# MSP430F5438A.net
KiCad netlist of a schematic drawn in Altium Designer
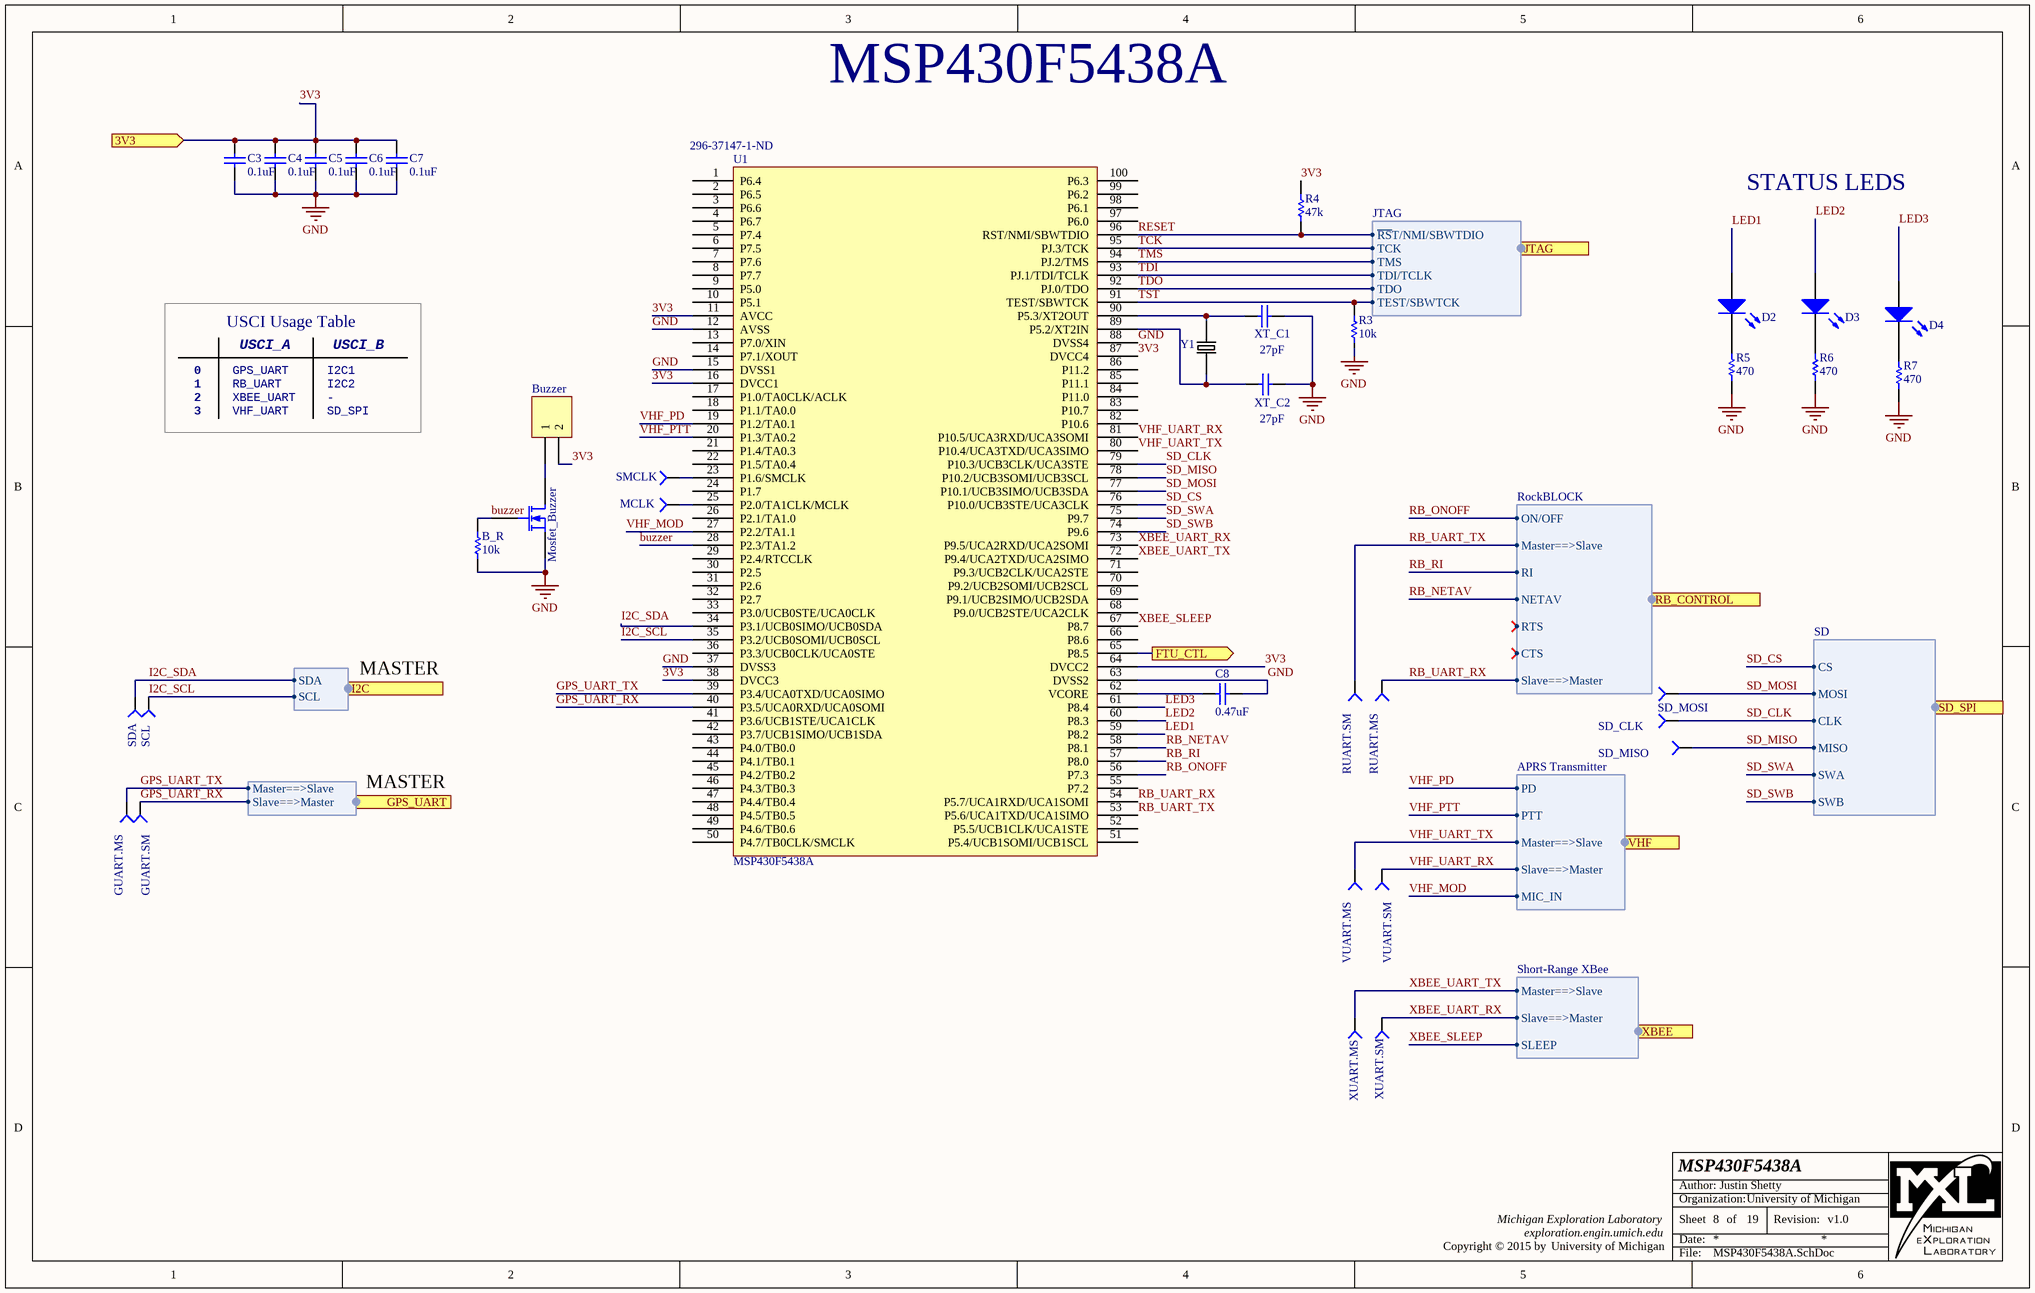
[diagram p0: MSP430F5438A.SchDoc]

(export (version "E")
  (design (tool "Eeschema 10.0.6"))
  (components
    (comp (ref "B_R")
      (value "10k")
      (footprint "J1-0603")
      (description "Resistive element")
      (fields (field (name "Comment") "Resistor"))
      (libsource (lib "MXLab Generic") (part "Resistor"))
    )
    (comp (ref "C3")
      (value "0.1uF")
      (footprint "1608[0603]")
      (description "Capacitor Ceramic")
      (libsource (lib "MXLab Generic") (part "Capacitor Ceramic"))
    )
    (comp (ref "C4")
      (value "0.1uF")
      (footprint "1608[0603]")
      (description "Capacitor Ceramic")
      (libsource (lib "MXLab Generic") (part "Capacitor Ceramic"))
    )
    (comp (ref "C5")
      (value "0.1uF")
      (footprint "1608[0603]")
      (description "Capacitor Ceramic")
      (libsource (lib "MXLab Generic") (part "Capacitor Ceramic"))
    )
    (comp (ref "C6")
      (value "0.1uF")
      (footprint "1608[0603]")
      (description "Capacitor Ceramic")
      (libsource (lib "MXLab Generic") (part "Capacitor Ceramic"))
    )
    (comp (ref "C7")
      (value "0.1uF")
      (footprint "1608[0603]")
      (description "Capacitor Ceramic")
      (libsource (lib "MXLab Generic") (part "Capacitor Ceramic"))
    )
    (comp (ref "C8")
      (value "0.47uF")
      (footprint "1608[0603]")
      (description "Capacitor Ceramic")
      (libsource (lib "MXLab Generic") (part "Capacitor Ceramic"))
    )
    (comp (ref "D2") (value "LED") (footprint "J1-0603") (libsource (lib "MXLab Generic") (part "LED")))
    (comp (ref "D3") (value "LED") (footprint "J1-0603") (libsource (lib "MXLab Generic") (part "LED")))
    (comp (ref "D4") (value "LED") (footprint "J1-0603") (libsource (lib "MXLab Generic") (part "LED")))
    (comp (ref "GUART.MS")
      (value "Testpoint")
      (footprint "TESTPOINT")
      (description "Probe point for testing")
      (libsource (lib "MXLab Generic") (part "Testpoint"))
    )
    (comp (ref "GUART.SM")
      (value "Testpoint")
      (footprint "TESTPOINT")
      (description "Probe point for testing")
      (libsource (lib "MXLab Generic") (part "Testpoint"))
    )
    (comp (ref "MCLK")
      (value "Testpoint")
      (footprint "TESTPOINT")
      (description "Probe point for testing")
      (libsource (lib "MXLab Generic") (part "Testpoint"))
    )
    (comp (ref "Mosfet_Buzzer")
      (value "MOSFET-N")
      (footprint "SOT-23_M")
      (description "N-Channel MOSFET")
      (fields (field (name "PUBLISHER") "Altium Limited"))
      (libsource (lib "Miscellaneous Devices") (part "MOSFET-N"))
    )
    (comp (ref "P4")
      (value "Buzzer")
      (footprint "Buzzer")
      (description "Header, 2-Pin")
      (fields (field (name "PUBLISHER") "Altium Limited"))
      (libsource (lib "Miscellaneous Connectors") (part "Header 2"))
    )
    (comp (ref "R3")
      (value "10k")
      (footprint "J1-0603")
      (description "Resistive element")
      (fields (field (name "Comment") "Resistor"))
      (libsource (lib "MXLab Generic") (part "Resistor"))
    )
    (comp (ref "R4")
      (value "47k")
      (footprint "J1-0603")
      (description "Resistive element")
      (fields (field (name "Comment") "Resistor"))
      (libsource (lib "MXLab Generic") (part "Resistor"))
    )
    (comp (ref "R5")
      (value "470")
      (footprint "J1-0603")
      (description "Resistive element")
      (fields (field (name "Comment") "Resistor"))
      (libsource (lib "MXLab Generic") (part "Resistor"))
    )
    (comp (ref "R6")
      (value "470")
      (footprint "J1-0603")
      (description "Resistive element")
      (fields (field (name "Comment") "Resistor"))
      (libsource (lib "MXLab Generic") (part "Resistor"))
    )
    (comp (ref "R7")
      (value "470")
      (footprint "J1-0603")
      (description "Resistive element")
      (fields (field (name "Comment") "Resistor"))
      (libsource (lib "MXLab Generic") (part "Resistor"))
    )
    (comp (ref "RUART.MS")
      (value "Testpoint")
      (footprint "TESTPOINT")
      (description "Probe point for testing")
      (libsource (lib "MXLab Generic") (part "Testpoint"))
    )
    (comp (ref "RUART.SM")
      (value "Testpoint")
      (footprint "TESTPOINT")
      (description "Probe point for testing")
      (libsource (lib "MXLab Generic") (part "Testpoint"))
    )
    (comp (ref "SCL")
      (value "Testpoint")
      (footprint "TESTPOINT")
      (description "Probe point for testing")
      (libsource (lib "MXLab Generic") (part "Testpoint"))
    )
    (comp (ref "SDA")
      (value "Testpoint")
      (footprint "TESTPOINT")
      (description "Probe point for testing")
      (libsource (lib "MXLab Generic") (part "Testpoint"))
    )
    (comp (ref "SD_CLK")
      (value "Testpoint")
      (footprint "TESTPOINT")
      (description "Probe point for testing")
      (libsource (lib "MXLab Generic") (part "Testpoint"))
    )
    (comp (ref "SD_MISO")
      (value "Testpoint")
      (footprint "TESTPOINT")
      (description "Probe point for testing")
      (libsource (lib "MXLab Generic") (part "Testpoint"))
    )
    (comp (ref "SD_MOSI")
      (value "Testpoint")
      (footprint "TESTPOINT")
      (description "Probe point for testing")
      (libsource (lib "MXLab Generic") (part "Testpoint"))
    )
    (comp (ref "SMCLK")
      (value "Testpoint")
      (footprint "TESTPOINT")
      (description "Probe point for testing")
      (libsource (lib "MXLab Generic") (part "Testpoint"))
    )
    (comp (ref "U1")
      (value "MSP430F5438A")
      (footprint "TSQFP50P1600X1600X160-100L")
      (fields
        (field (name "SUPPLIER PART NUMBER 1") "296-37147-1-ND")
        (field (name "MANUFACTURER") "Texas Instruments")
        (field (name "MANUFACTURER PART NUMBER") "MSP430F5438AIPZR")
      )
      (libsource (lib "ATACS_SCH_LIB") (part "MSP430F438IPZ"))
    )
    (comp (ref "VUART.MS")
      (value "Testpoint")
      (footprint "TESTPOINT")
      (description "Probe point for testing")
      (libsource (lib "MXLab Generic") (part "Testpoint"))
    )
    (comp (ref "VUART.SM")
      (value "Testpoint")
      (footprint "TESTPOINT")
      (description "Probe point for testing")
      (libsource (lib "MXLab Generic") (part "Testpoint"))
    )
    (comp (ref "XT_C1")
      (value "27pF")
      (footprint "1608[0603]")
      (description "Capacitor Ceramic")
      (libsource (lib "MXLab Generic") (part "Capacitor Ceramic"))
    )
    (comp (ref "XT_C2")
      (value "27pF")
      (footprint "1608[0603]")
      (description "Capacitor Ceramic")
      (libsource (lib "MXLab Generic") (part "Capacitor Ceramic"))
    )
    (comp (ref "XUART.MS")
      (value "Testpoint")
      (footprint "TESTPOINT")
      (description "Probe point for testing")
      (libsource (lib "MXLab Generic") (part "Testpoint"))
    )
    (comp (ref "XUART.SM")
      (value "Testpoint")
      (footprint "TESTPOINT")
      (description "Probe point for testing")
      (libsource (lib "MXLab Generic") (part "Testpoint"))
    )
    (comp (ref "Y1")
      (value "ECS-160-18-5PXEN-TR")
      (footprint "*XTAL_ECS-160-18-5PXEN-TR")
      (description "Crystal 16MHz 18pF 2-Pin SMD T/R")
      (fields (field (name "DIGI-KEY_PART_NUMBER") "XC1695CT-ND") (field (name "MF") "ECS Inc."))
      (libsource (lib "ATACS_SCH_LIB") (part "ECS-160-18-5PXEN-TR"))
    )
  )
  (nets
    (net (code "10") (name "/3V3") (class "Default")
      (node (ref "C3") (pin "2") (pinfunction "2_2") (pintype "passive"))
      (node (ref "C4") (pin "2") (pinfunction "2_2") (pintype "passive"))
      (node (ref "C5") (pin "2") (pinfunction "2_2") (pintype "passive"))
      (node (ref "C6") (pin "2") (pinfunction "2_2") (pintype "passive"))
      (node (ref "C7") (pin "2") (pinfunction "2_2") (pintype "passive"))
      (node (ref "P4") (pin "2") (pinfunction "2_2") (pintype "passive"))
      (node (ref "R4") (pin "1") (pinfunction "1_1") (pintype "passive"))
      (node (ref "U1") (pin "11") (pinfunction "AVCC_11") (pintype "passive"))
      (node (ref "U1") (pin "16") (pinfunction "DVCC1_16") (pintype "passive"))
      (node (ref "U1") (pin "38") (pinfunction "DVCC3_38") (pintype "passive"))
      (node (ref "U1") (pin "64") (pinfunction "DVCC2_64") (pintype "passive"))
      (node (ref "U1") (pin "87") (pinfunction "DVCC4_87") (pintype "passive"))
    )
    (net (code "11") (name "/FTU_CTL") (class "Default")
      (node (ref "U1") (pin "65") (pinfunction "P8.5_65") (pintype "passive"))
    )
    (net (code "12") (name "/GPS_UART_RX") (class "Default")
      (node (ref "GUART.SM") (pin "1") (pinfunction "1_1") (pintype "passive"))
      (node (ref "U1") (pin "40") (pinfunction "P3.5/UCA0RXD/UCA0SOMI_40") (pintype "passive"))
    )
    (net (code "13") (name "/GPS_UART_TX") (class "Default")
      (node (ref "GUART.MS") (pin "1") (pinfunction "1_1") (pintype "passive"))
      (node (ref "U1") (pin "39") (pinfunction "P3.4/UCA0TXD/UCA0SIMO_39") (pintype "passive"))
    )
    (net (code "14") (name "/I2C_SCL") (class "Default")
      (node (ref "SCL") (pin "1") (pinfunction "1_1") (pintype "passive"))
      (node (ref "U1") (pin "35") (pinfunction "P3.2/UCB0SOMI/UCB0SCL_35") (pintype "passive"))
    )
    (net (code "15") (name "/I2C_SDA") (class "Default")
      (node (ref "SDA") (pin "1") (pinfunction "1_1") (pintype "passive"))
      (node (ref "U1") (pin "34") (pinfunction "P3.1/UCB0SIMO/UCB0SDA_34") (pintype "passive"))
    )
    (net (code "16") (name "/LED1") (class "Default")
      (node (ref "D2") (pin "2") (pinfunction "K_2") (pintype "passive"))
      (node (ref "U1") (pin "59") (pinfunction "P8.2_59") (pintype "passive"))
    )
    (net (code "17") (name "/LED2") (class "Default")
      (node (ref "D3") (pin "2") (pinfunction "K_2") (pintype "passive"))
      (node (ref "U1") (pin "60") (pinfunction "P8.3_60") (pintype "passive"))
    )
    (net (code "18") (name "/LED3") (class "Default")
      (node (ref "D4") (pin "2") (pinfunction "K_2") (pintype "passive"))
      (node (ref "U1") (pin "61") (pinfunction "P8.4_61") (pintype "passive"))
    )
    (net (code "19") (name "/RB_NETAV") (class "Default")
      (node (ref "U1") (pin "58") (pinfunction "P8.1_58") (pintype "passive"))
    )
    (net (code "20") (name "/RB_ONOFF") (class "Default")
      (node (ref "U1") (pin "56") (pinfunction "P7.3_56") (pintype "passive"))
    )
    (net (code "21") (name "/RB_RI") (class "Default")
      (node (ref "U1") (pin "57") (pinfunction "P8.0_57") (pintype "passive"))
    )
    (net (code "22") (name "/RB_UART_RX") (class "Default")
      (node (ref "RUART.MS") (pin "1") (pinfunction "1_1") (pintype "passive"))
      (node (ref "U1") (pin "54") (pinfunction "P5.7/UCA1RXD/UCA1SOMI_54") (pintype "passive"))
    )
    (net (code "23") (name "/RB_UART_TX") (class "Default")
      (node (ref "RUART.SM") (pin "1") (pinfunction "1_1") (pintype "passive"))
      (node (ref "U1") (pin "53") (pinfunction "P5.6/UCA1TXD/UCA1SIMO_53") (pintype "passive"))
    )
    (net (code "24") (name "/RESET") (class "Default")
      (node (ref "R4") (pin "2") (pinfunction "2_2") (pintype "passive"))
      (node (ref "U1") (pin "96") (pinfunction "RST/NMI/SBWTDIO_96") (pintype "passive"))
    )
    (net (code "25") (name "/SD_CLK") (class "Default")
      (node (ref "SD_CLK") (pin "1") (pinfunction "1_1") (pintype "passive"))
      (node (ref "U1") (pin "79") (pinfunction "P10.3/UCB3CLK/UCA3STE_79") (pintype "passive"))
    )
    (net (code "26") (name "/SD_CS") (class "Default")
      (node (ref "U1") (pin "76") (pinfunction "P10.0/UCB3STE/UCA3CLK_76") (pintype "passive"))
    )
    (net (code "27") (name "/SD_MISO") (class "Default")
      (node (ref "SD_MISO") (pin "1") (pinfunction "1_1") (pintype "passive"))
      (node (ref "U1") (pin "78") (pinfunction "P10.2/UCB3SOMI/UCB3SCL_78") (pintype "passive"))
    )
    (net (code "28") (name "/SD_MOSI") (class "Default")
      (node (ref "SD_MOSI") (pin "1") (pinfunction "1_1") (pintype "passive"))
      (node (ref "U1") (pin "77") (pinfunction "P10.1/UCB3SIMO/UCB3SDA_77") (pintype "passive"))
    )
    (net (code "29") (name "/SD_SWA") (class "Default")
      (node (ref "U1") (pin "75") (pinfunction "P9.7_75") (pintype "passive"))
    )
    (net (code "30") (name "/SD_SWB") (class "Default")
      (node (ref "U1") (pin "74") (pinfunction "P9.6_74") (pintype "passive"))
    )
    (net (code "31") (name "/TCK") (class "Default")
      (node (ref "U1") (pin "95") (pinfunction "PJ.3/TCK_95") (pintype "passive"))
    )
    (net (code "32") (name "/TDI") (class "Default")
      (node (ref "U1") (pin "93") (pinfunction "PJ.1/TDI/TCLK_93") (pintype "passive"))
    )
    (net (code "33") (name "/TDO") (class "Default")
      (node (ref "U1") (pin "92") (pinfunction "PJ.0/TDO_92") (pintype "passive"))
    )
    (net (code "34") (name "/TMS") (class "Default")
      (node (ref "U1") (pin "94") (pinfunction "PJ.2/TMS_94") (pintype "passive"))
    )
    (net (code "35") (name "/TST") (class "Default")
      (node (ref "R3") (pin "2") (pinfunction "2_2") (pintype "passive"))
      (node (ref "U1") (pin "91") (pinfunction "TEST/SBWTCK_91") (pintype "passive"))
    )
    (net (code "36") (name "/VHF_MOD") (class "Default")
      (node (ref "U1") (pin "27") (pinfunction "P2.2/TA1.1_27") (pintype "passive"))
    )
    (net (code "37") (name "/VHF_PD") (class "Default")
      (node (ref "U1") (pin "19") (pinfunction "P1.2/TA0.1_19") (pintype "passive"))
    )
    (net (code "38") (name "/VHF_PTT") (class "Default")
      (node (ref "U1") (pin "20") (pinfunction "P1.3/TA0.2_20") (pintype "passive"))
    )
    (net (code "39") (name "/VHF_UART_RX") (class "Default")
      (node (ref "U1") (pin "81") (pinfunction "P10.5/UCA3RXD/UCA3SOMI_81") (pintype "passive"))
      (node (ref "VUART.SM") (pin "1") (pinfunction "1_1") (pintype "passive"))
    )
    (net (code "40") (name "/VHF_UART_TX") (class "Default")
      (node (ref "U1") (pin "80") (pinfunction "P10.4/UCA3TXD/UCA3SIMO_80") (pintype "passive"))
      (node (ref "VUART.MS") (pin "1") (pinfunction "1_1") (pintype "passive"))
    )
    (net (code "41") (name "/XBEE_SLEEP") (class "Default")
      (node (ref "U1") (pin "67") (pinfunction "P8.7_67") (pintype "passive"))
    )
    (net (code "42") (name "/XBEE_UART_RX") (class "Default")
      (node (ref "U1") (pin "73") (pinfunction "P9.5/UCA2RXD/UCA2SOMI_73") (pintype "passive"))
      (node (ref "XUART.SM") (pin "1") (pinfunction "1_1") (pintype "passive"))
    )
    (net (code "43") (name "/XBEE_UART_TX") (class "Default")
      (node (ref "U1") (pin "72") (pinfunction "P9.4/UCA2TXD/UCA2SIMO_72") (pintype "passive"))
      (node (ref "XUART.MS") (pin "1") (pinfunction "1_1") (pintype "passive"))
    )
    (net (code "44") (name "/buzzer") (class "Default")
      (node (ref "B_R") (pin "2") (pinfunction "2_2") (pintype "passive"))
      (node (ref "Mosfet_Buzzer") (pin "2") (pinfunction "G_2") (pintype "passive"))
      (node (ref "U1") (pin "28") (pinfunction "P2.3/TA1.2_28") (pintype "passive"))
    )
    (net (code "52") (name "GND") (class "Default")
      (node (ref "B_R") (pin "1") (pinfunction "1_1") (pintype "passive"))
      (node (ref "C3") (pin "1") (pinfunction "1_1") (pintype "passive"))
      (node (ref "C4") (pin "1") (pinfunction "1_1") (pintype "passive"))
      (node (ref "C5") (pin "1") (pinfunction "1_1") (pintype "passive"))
      (node (ref "C6") (pin "1") (pinfunction "1_1") (pintype "passive"))
      (node (ref "C7") (pin "1") (pinfunction "1_1") (pintype "passive"))
      (node (ref "C8") (pin "2") (pinfunction "2_2") (pintype "passive"))
      (node (ref "Mosfet_Buzzer") (pin "3") (pinfunction "S_3") (pintype "passive"))
      (node (ref "R3") (pin "1") (pinfunction "1_1") (pintype "passive"))
      (node (ref "R5") (pin "1") (pinfunction "1_1") (pintype "passive"))
      (node (ref "R6") (pin "1") (pinfunction "1_1") (pintype "passive"))
      (node (ref "R7") (pin "1") (pinfunction "1_1") (pintype "passive"))
      (node (ref "U1") (pin "12") (pinfunction "AVSS_12") (pintype "passive"))
      (node (ref "U1") (pin "15") (pinfunction "DVSS1_15") (pintype "passive"))
      (node (ref "U1") (pin "37") (pinfunction "DVSS3_37") (pintype "passive"))
      (node (ref "U1") (pin "63") (pinfunction "DVSS2_63") (pintype "passive"))
      (node (ref "U1") (pin "88") (pinfunction "DVSS4_88") (pintype "passive"))
      (node (ref "XT_C1") (pin "1") (pinfunction "1_1") (pintype "passive"))
      (node (ref "XT_C2") (pin "1") (pinfunction "1_1") (pintype "passive"))
    )
    (net (code "53") (name "Net-(D2-A)") (class "Default")
      (node (ref "D2") (pin "1") (pinfunction "A_1") (pintype "passive"))
      (node (ref "R5") (pin "2") (pinfunction "2_2") (pintype "passive"))
    )
    (net (code "54") (name "Net-(D3-A)") (class "Default")
      (node (ref "D3") (pin "1") (pinfunction "A_1") (pintype "passive"))
      (node (ref "R6") (pin "2") (pinfunction "2_2") (pintype "passive"))
    )
    (net (code "55") (name "Net-(D4-A)") (class "Default")
      (node (ref "D4") (pin "1") (pinfunction "A_1") (pintype "passive"))
      (node (ref "R7") (pin "2") (pinfunction "2_2") (pintype "passive"))
    )
    (net (code "56") (name "Net-(Mosfet_Buzzer-D)") (class "Default")
      (node (ref "Mosfet_Buzzer") (pin "1") (pinfunction "D_1") (pintype "passive"))
      (node (ref "P4") (pin "1") (pinfunction "1_1") (pintype "passive"))
    )
    (net (code "57") (name "Net-(U1-P1.6{slash}SMCLK)") (class "Default")
      (node (ref "SMCLK") (pin "1") (pinfunction "1_1") (pintype "passive"))
      (node (ref "U1") (pin "23") (pinfunction "P1.6/SMCLK_23") (pintype "passive"))
    )
    (net (code "58") (name "Net-(U1-P2.0{slash}TA1CLK{slash}MCLK)") (class "Default")
      (node (ref "MCLK") (pin "1") (pinfunction "1_1") (pintype "passive"))
      (node (ref "U1") (pin "25") (pinfunction "P2.0/TA1CLK/MCLK_25") (pintype "passive"))
    )
    (net (code "59") (name "Net-(U1-P5.2{slash}XT2IN)") (class "Default")
      (node (ref "U1") (pin "89") (pinfunction "P5.2/XT2IN_89") (pintype "passive"))
      (node (ref "XT_C2") (pin "2") (pinfunction "2_2") (pintype "passive"))
      (node (ref "Y1") (pin "1") (pinfunction "1_1") (pintype "passive"))
    )
    (net (code "60") (name "Net-(U1-P5.3{slash}XT2OUT)") (class "Default")
      (node (ref "U1") (pin "90") (pinfunction "P5.3/XT2OUT_90") (pintype "passive"))
      (node (ref "XT_C1") (pin "2") (pinfunction "2_2") (pintype "passive"))
      (node (ref "Y1") (pin "2") (pinfunction "2_2") (pintype "passive"))
    )
    (net (code "61") (name "Net-(U1-VCORE)") (class "Default")
      (node (ref "C8") (pin "1") (pinfunction "1_1") (pintype "passive"))
      (node (ref "U1") (pin "62") (pinfunction "VCORE_62") (pintype "passive"))
    )
    (net (code "62") (name "unconnected-(U1-P1.0{slash}TA0CLK{slash}ACLK-Pad17)") (class "Default")
      (node (ref "U1") (pin "17") (pinfunction "P1.0/TA0CLK/ACLK_17") (pintype "passive"))
    )
    (net (code "63") (name "unconnected-(U1-P1.1{slash}TA0.0-Pad18)") (class "Default")
      (node (ref "U1") (pin "18") (pinfunction "P1.1/TA0.0_18") (pintype "passive"))
    )
    (net (code "64") (name "unconnected-(U1-P1.4{slash}TA0.3-Pad21)") (class "Default")
      (node (ref "U1") (pin "21") (pinfunction "P1.4/TA0.3_21") (pintype "passive"))
    )
    (net (code "65") (name "unconnected-(U1-P1.5{slash}TA0.4-Pad22)") (class "Default")
      (node (ref "U1") (pin "22") (pinfunction "P1.5/TA0.4_22") (pintype "passive"))
    )
    (net (code "66") (name "unconnected-(U1-P1.7-Pad24)") (class "Default")
      (node (ref "U1") (pin "24") (pinfunction "P1.7_24") (pintype "passive"))
    )
    (net (code "67") (name "unconnected-(U1-P2.1{slash}TA1.0-Pad26)") (class "Default")
      (node (ref "U1") (pin "26") (pinfunction "P2.1/TA1.0_26") (pintype "passive"))
    )
    (net (code "68") (name "unconnected-(U1-P2.4{slash}RTCCLK-Pad29)") (class "Default")
      (node (ref "U1") (pin "29") (pinfunction "P2.4/RTCCLK_29") (pintype "passive"))
    )
    (net (code "69") (name "unconnected-(U1-P2.5-Pad30)") (class "Default")
      (node (ref "U1") (pin "30") (pinfunction "P2.5_30") (pintype "passive"))
    )
    (net (code "70") (name "unconnected-(U1-P2.6-Pad31)") (class "Default")
      (node (ref "U1") (pin "31") (pinfunction "P2.6_31") (pintype "passive"))
    )
    (net (code "71") (name "unconnected-(U1-P2.7-Pad32)") (class "Default")
      (node (ref "U1") (pin "32") (pinfunction "P2.7_32") (pintype "passive"))
    )
    (net (code "72") (name "unconnected-(U1-P3.0{slash}UCB0STE{slash}UCA0CLK-Pad33)") (class "Default")
      (node (ref "U1") (pin "33") (pinfunction "P3.0/UCB0STE/UCA0CLK_33") (pintype "passive"))
    )
    (net (code "73") (name "unconnected-(U1-P3.3{slash}UCB0CLK{slash}UCA0STE-Pad36)") (class "Default")
      (node (ref "U1") (pin "36") (pinfunction "P3.3/UCB0CLK/UCA0STE_36") (pintype "passive"))
    )
    (net (code "74") (name "unconnected-(U1-P3.6{slash}UCB1STE{slash}UCA1CLK-Pad41)") (class "Default")
      (node (ref "U1") (pin "41") (pinfunction "P3.6/UCB1STE/UCA1CLK_41") (pintype "passive"))
    )
    (net (code "75") (name "unconnected-(U1-P3.7{slash}UCB1SIMO{slash}UCB1SDA-Pad42)") (class "Default")
      (node (ref "U1") (pin "42") (pinfunction "P3.7/UCB1SIMO/UCB1SDA_42") (pintype "passive"))
    )
    (net (code "76") (name "unconnected-(U1-P4.0{slash}TB0.0-Pad43)") (class "Default")
      (node (ref "U1") (pin "43") (pinfunction "P4.0/TB0.0_43") (pintype "passive"))
    )
    (net (code "77") (name "unconnected-(U1-P4.1{slash}TB0.1-Pad44)") (class "Default")
      (node (ref "U1") (pin "44") (pinfunction "P4.1/TB0.1_44") (pintype "passive"))
    )
    (net (code "78") (name "unconnected-(U1-P4.2{slash}TB0.2-Pad45)") (class "Default")
      (node (ref "U1") (pin "45") (pinfunction "P4.2/TB0.2_45") (pintype "passive"))
    )
    (net (code "79") (name "unconnected-(U1-P4.3{slash}TB0.3-Pad46)") (class "Default")
      (node (ref "U1") (pin "46") (pinfunction "P4.3/TB0.3_46") (pintype "passive"))
    )
    (net (code "80") (name "unconnected-(U1-P4.4{slash}TB0.4-Pad47)") (class "Default")
      (node (ref "U1") (pin "47") (pinfunction "P4.4/TB0.4_47") (pintype "passive"))
    )
    (net (code "81") (name "unconnected-(U1-P4.5{slash}TB0.5-Pad48)") (class "Default")
      (node (ref "U1") (pin "48") (pinfunction "P4.5/TB0.5_48") (pintype "passive"))
    )
    (net (code "82") (name "unconnected-(U1-P4.6{slash}TB0.6-Pad49)") (class "Default")
      (node (ref "U1") (pin "49") (pinfunction "P4.6/TB0.6_49") (pintype "passive"))
    )
    (net (code "83") (name "unconnected-(U1-P4.7{slash}TB0CLK{slash}SMCLK-Pad50)") (class "Default")
      (node (ref "U1") (pin "50") (pinfunction "P4.7/TB0CLK/SMCLK_50") (pintype "passive"))
    )
    (net (code "84") (name "unconnected-(U1-P5.0-Pad9)") (class "Default")
      (node (ref "U1") (pin "9") (pinfunction "P5.0_9") (pintype "passive"))
    )
    (net (code "85") (name "unconnected-(U1-P5.1-Pad10)") (class "Default")
      (node (ref "U1") (pin "10") (pinfunction "P5.1_10") (pintype "passive"))
    )
    (net (code "86") (name "unconnected-(U1-P5.4{slash}UCB1SOMI{slash}UCB1SCL-Pad51)") (class "Default")
      (node (ref "U1") (pin "51") (pinfunction "P5.4/UCB1SOMI/UCB1SCL_51") (pintype "passive"))
    )
    (net (code "87") (name "unconnected-(U1-P5.5{slash}UCB1CLK{slash}UCA1STE-Pad52)") (class "Default")
      (node (ref "U1") (pin "52") (pinfunction "P5.5/UCB1CLK/UCA1STE_52") (pintype "passive"))
    )
    (net (code "88") (name "unconnected-(U1-P6.0-Pad97)") (class "Default")
      (node (ref "U1") (pin "97") (pinfunction "P6.0_97") (pintype "passive"))
    )
    (net (code "89") (name "unconnected-(U1-P6.1-Pad98)") (class "Default")
      (node (ref "U1") (pin "98") (pinfunction "P6.1_98") (pintype "passive"))
    )
    (net (code "90") (name "unconnected-(U1-P6.2-Pad99)") (class "Default")
      (node (ref "U1") (pin "99") (pinfunction "P6.2_99") (pintype "passive"))
    )
    (net (code "91") (name "unconnected-(U1-P6.3-Pad100)") (class "Default")
      (node (ref "U1") (pin "100") (pinfunction "P6.3_100") (pintype "passive"))
    )
    (net (code "92") (name "unconnected-(U1-P6.4-Pad1)") (class "Default")
      (node (ref "U1") (pin "1") (pinfunction "P6.4_1") (pintype "passive"))
    )
    (net (code "93") (name "unconnected-(U1-P6.5-Pad2)") (class "Default")
      (node (ref "U1") (pin "2") (pinfunction "P6.5_2") (pintype "passive"))
    )
    (net (code "94") (name "unconnected-(U1-P6.6-Pad3)") (class "Default")
      (node (ref "U1") (pin "3") (pinfunction "P6.6_3") (pintype "passive"))
    )
    (net (code "95") (name "unconnected-(U1-P6.7-Pad4)") (class "Default")
      (node (ref "U1") (pin "4") (pinfunction "P6.7_4") (pintype "passive"))
    )
    (net (code "96") (name "unconnected-(U1-P7.0{slash}XIN-Pad13)") (class "Default")
      (node (ref "U1") (pin "13") (pinfunction "P7.0/XIN_13") (pintype "passive"))
    )
    (net (code "97") (name "unconnected-(U1-P7.1{slash}XOUT-Pad14)") (class "Default")
      (node (ref "U1") (pin "14") (pinfunction "P7.1/XOUT_14") (pintype "passive"))
    )
    (net (code "98") (name "unconnected-(U1-P7.2-Pad55)") (class "Default")
      (node (ref "U1") (pin "55") (pinfunction "P7.2_55") (pintype "passive"))
    )
    (net (code "99") (name "unconnected-(U1-P7.4-Pad5)") (class "Default")
      (node (ref "U1") (pin "5") (pinfunction "P7.4_5") (pintype "passive"))
    )
    (net (code "100") (name "unconnected-(U1-P7.5-Pad6)") (class "Default")
      (node (ref "U1") (pin "6") (pinfunction "P7.5_6") (pintype "passive"))
    )
    (net (code "101") (name "unconnected-(U1-P7.6-Pad7)") (class "Default")
      (node (ref "U1") (pin "7") (pinfunction "P7.6_7") (pintype "passive"))
    )
    (net (code "102") (name "unconnected-(U1-P7.7-Pad8)") (class "Default")
      (node (ref "U1") (pin "8") (pinfunction "P7.7_8") (pintype "passive"))
    )
    (net (code "103") (name "unconnected-(U1-P8.6-Pad66)") (class "Default")
      (node (ref "U1") (pin "66") (pinfunction "P8.6_66") (pintype "passive"))
    )
    (net (code "104") (name "unconnected-(U1-P9.0{slash}UCB2STE{slash}UCA2CLK-Pad68)") (class "Default")
      (node (ref "U1") (pin "68") (pinfunction "P9.0/UCB2STE/UCA2CLK_68") (pintype "passive"))
    )
    (net (code "105") (name "unconnected-(U1-P9.1{slash}UCB2SIMO{slash}UCB2SDA-Pad69)") (class "Default")
      (node (ref "U1") (pin "69") (pinfunction "P9.1/UCB2SIMO/UCB2SDA_69") (pintype "passive"))
    )
    (net (code "106") (name "unconnected-(U1-P9.2{slash}UCB2SOMI{slash}UCB2SCL-Pad70)") (class "Default")
      (node (ref "U1") (pin "70") (pinfunction "P9.2/UCB2SOMI/UCB2SCL_70") (pintype "passive"))
    )
    (net (code "107") (name "unconnected-(U1-P9.3{slash}UCB2CLK{slash}UCA2STE-Pad71)") (class "Default")
      (node (ref "U1") (pin "71") (pinfunction "P9.3/UCB2CLK/UCA2STE_71") (pintype "passive"))
    )
    (net (code "108") (name "unconnected-(U1-P10.6-Pad82)") (class "Default")
      (node (ref "U1") (pin "82") (pinfunction "P10.6_82") (pintype "passive"))
    )
    (net (code "109") (name "unconnected-(U1-P10.7-Pad83)") (class "Default")
      (node (ref "U1") (pin "83") (pinfunction "P10.7_83") (pintype "passive"))
    )
    (net (code "110") (name "unconnected-(U1-P11.0-Pad84)") (class "Default")
      (node (ref "U1") (pin "84") (pinfunction "P11.0_84") (pintype "passive"))
    )
    (net (code "111") (name "unconnected-(U1-P11.1-Pad85)") (class "Default")
      (node (ref "U1") (pin "85") (pinfunction "P11.1_85") (pintype "passive"))
    )
    (net (code "112") (name "unconnected-(U1-P11.2-Pad86)") (class "Default")
      (node (ref "U1") (pin "86") (pinfunction "P11.2_86") (pintype "passive"))
    )
  )
)
